# Sheet1.net
KiCad netlist of a schematic drawn in Altium Designer
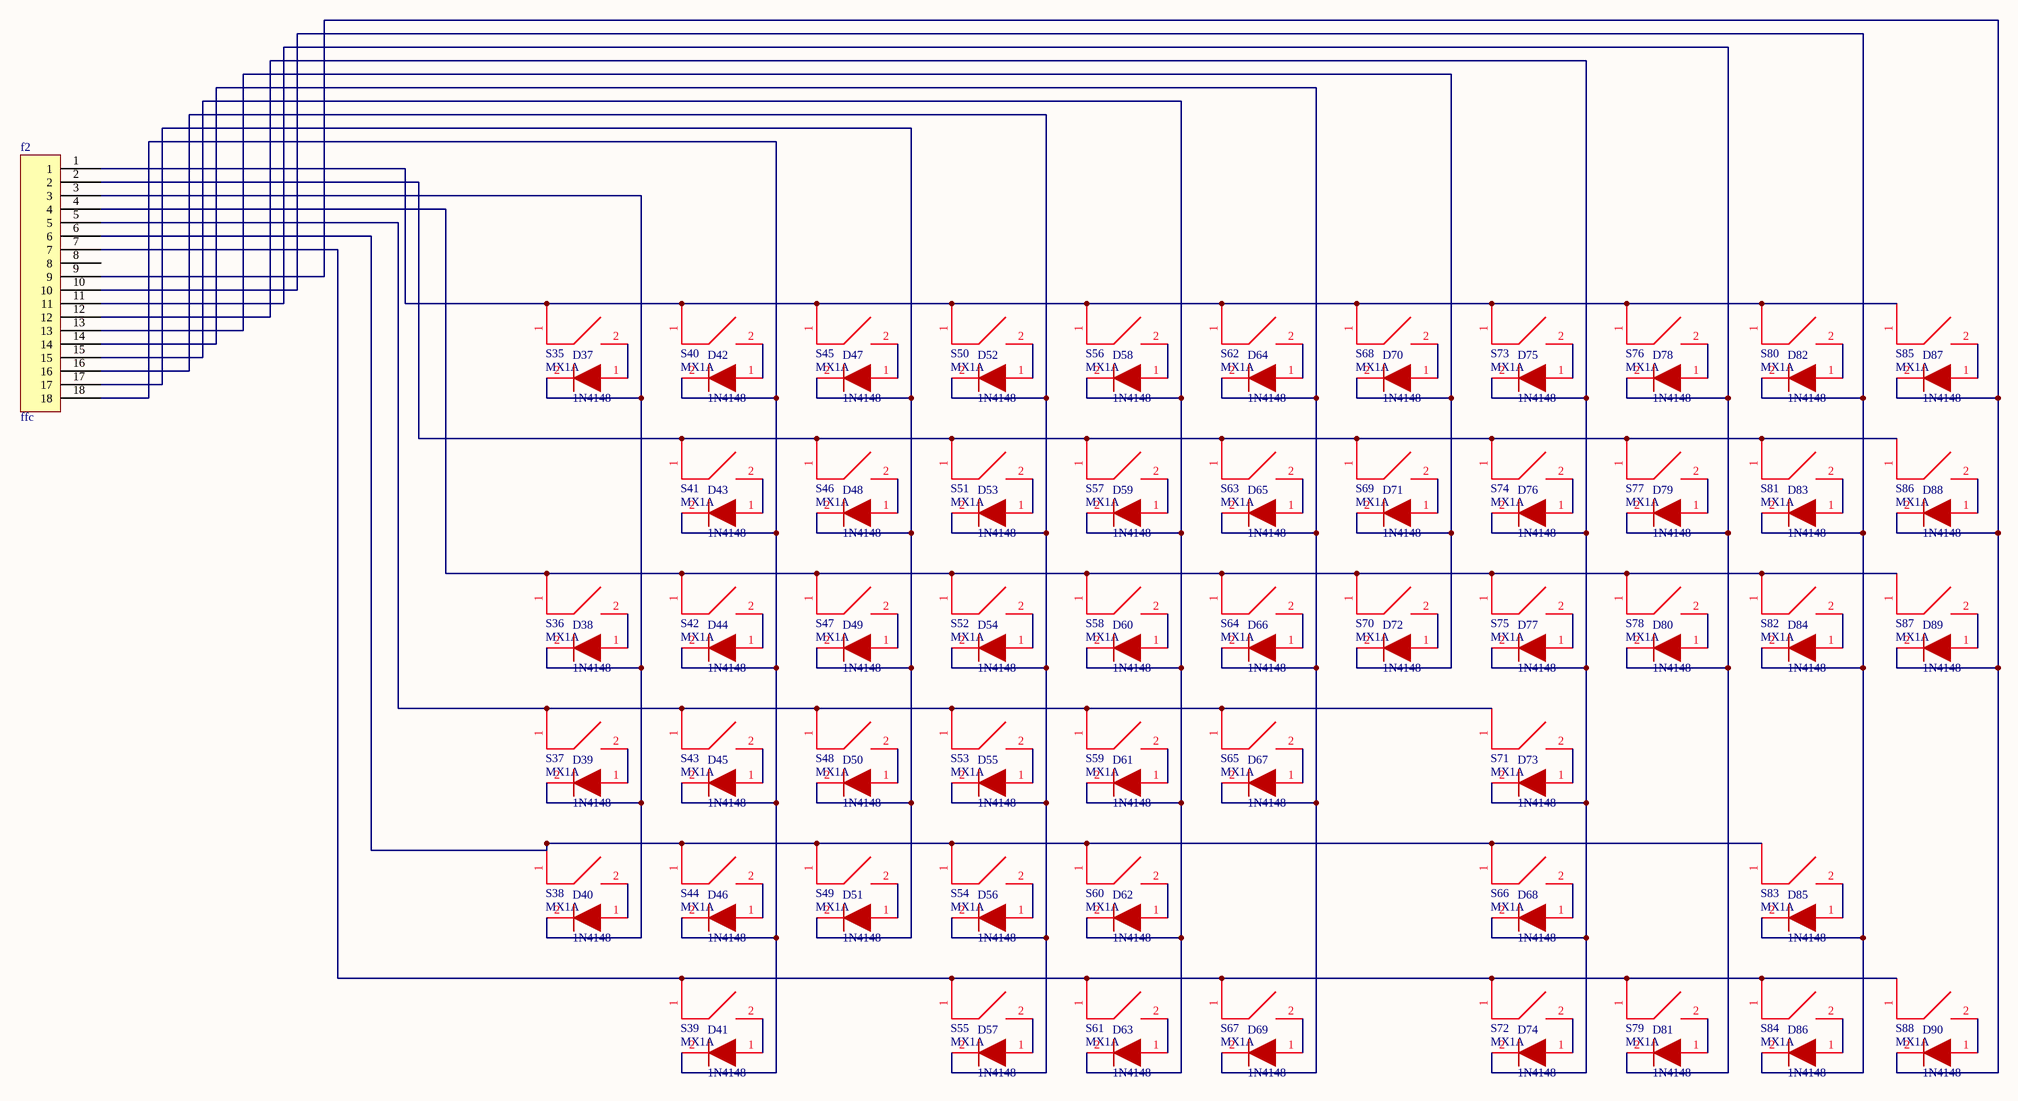
[diagram p0: Sheet1.SchDoc]

(export (version "E")
  (design (tool "Eeschema 10.0.6"))
  (components
    (comp (ref "D37")
      (value "1N4148")
      (footprint "SOD323")
      (description "二极管")
      (libsource (lib "keyboard") (part "1N4148"))
    )
    (comp (ref "D38")
      (value "1N4148")
      (footprint "SOD323")
      (description "二极管")
      (libsource (lib "keyboard") (part "1N4148"))
    )
    (comp (ref "D39")
      (value "1N4148")
      (footprint "SOD323")
      (description "二极管")
      (libsource (lib "keyboard") (part "1N4148"))
    )
    (comp (ref "D40")
      (value "1N4148")
      (footprint "SOD323")
      (description "二极管")
      (libsource (lib "keyboard") (part "1N4148"))
    )
    (comp (ref "D41")
      (value "1N4148")
      (footprint "SOD323")
      (description "二极管")
      (libsource (lib "keyboard") (part "1N4148"))
    )
    (comp (ref "D42")
      (value "1N4148")
      (footprint "SOD323")
      (description "二极管")
      (libsource (lib "keyboard") (part "1N4148"))
    )
    (comp (ref "D43")
      (value "1N4148")
      (footprint "SOD323")
      (description "二极管")
      (libsource (lib "keyboard") (part "1N4148"))
    )
    (comp (ref "D44")
      (value "1N4148")
      (footprint "SOD323")
      (description "二极管")
      (libsource (lib "keyboard") (part "1N4148"))
    )
    (comp (ref "D45")
      (value "1N4148")
      (footprint "SOD323")
      (description "二极管")
      (libsource (lib "keyboard") (part "1N4148"))
    )
    (comp (ref "D46")
      (value "1N4148")
      (footprint "SOD323")
      (description "二极管")
      (libsource (lib "keyboard") (part "1N4148"))
    )
    (comp (ref "D47")
      (value "1N4148")
      (footprint "SOD323")
      (description "二极管")
      (libsource (lib "keyboard") (part "1N4148"))
    )
    (comp (ref "D48")
      (value "1N4148")
      (footprint "SOD323")
      (description "二极管")
      (libsource (lib "keyboard") (part "1N4148"))
    )
    (comp (ref "D49")
      (value "1N4148")
      (footprint "SOD323")
      (description "二极管")
      (libsource (lib "keyboard") (part "1N4148"))
    )
    (comp (ref "D50")
      (value "1N4148")
      (footprint "SOD323")
      (description "二极管")
      (libsource (lib "keyboard") (part "1N4148"))
    )
    (comp (ref "D51")
      (value "1N4148")
      (footprint "SOD323")
      (description "二极管")
      (libsource (lib "keyboard") (part "1N4148"))
    )
    (comp (ref "D52")
      (value "1N4148")
      (footprint "SOD323")
      (description "二极管")
      (libsource (lib "keyboard") (part "1N4148"))
    )
    (comp (ref "D53")
      (value "1N4148")
      (footprint "SOD323")
      (description "二极管")
      (libsource (lib "keyboard") (part "1N4148"))
    )
    (comp (ref "D54")
      (value "1N4148")
      (footprint "SOD323")
      (description "二极管")
      (libsource (lib "keyboard") (part "1N4148"))
    )
    (comp (ref "D55")
      (value "1N4148")
      (footprint "SOD323")
      (description "二极管")
      (libsource (lib "keyboard") (part "1N4148"))
    )
    (comp (ref "D56")
      (value "1N4148")
      (footprint "SOD323")
      (description "二极管")
      (libsource (lib "keyboard") (part "1N4148"))
    )
    (comp (ref "D57")
      (value "1N4148")
      (footprint "SOD323")
      (description "二极管")
      (libsource (lib "keyboard") (part "1N4148"))
    )
    (comp (ref "D58")
      (value "1N4148")
      (footprint "SOD323")
      (description "二极管")
      (libsource (lib "keyboard") (part "1N4148"))
    )
    (comp (ref "D59")
      (value "1N4148")
      (footprint "SOD323")
      (description "二极管")
      (libsource (lib "keyboard") (part "1N4148"))
    )
    (comp (ref "D60")
      (value "1N4148")
      (footprint "SOD323")
      (description "二极管")
      (libsource (lib "keyboard") (part "1N4148"))
    )
    (comp (ref "D61")
      (value "1N4148")
      (footprint "SOD323")
      (description "二极管")
      (libsource (lib "keyboard") (part "1N4148"))
    )
    (comp (ref "D62")
      (value "1N4148")
      (footprint "SOD323")
      (description "二极管")
      (libsource (lib "keyboard") (part "1N4148"))
    )
    (comp (ref "D63")
      (value "1N4148")
      (footprint "SOD323")
      (description "二极管")
      (libsource (lib "keyboard") (part "1N4148"))
    )
    (comp (ref "D64")
      (value "1N4148")
      (footprint "SOD323")
      (description "二极管")
      (libsource (lib "keyboard") (part "1N4148"))
    )
    (comp (ref "D65")
      (value "1N4148")
      (footprint "SOD323")
      (description "二极管")
      (libsource (lib "keyboard") (part "1N4148"))
    )
    (comp (ref "D66")
      (value "1N4148")
      (footprint "SOD323")
      (description "二极管")
      (libsource (lib "keyboard") (part "1N4148"))
    )
    (comp (ref "D67")
      (value "1N4148")
      (footprint "SOD323")
      (description "二极管")
      (libsource (lib "keyboard") (part "1N4148"))
    )
    (comp (ref "D68")
      (value "1N4148")
      (footprint "SOD323")
      (description "二极管")
      (libsource (lib "keyboard") (part "1N4148"))
    )
    (comp (ref "D69")
      (value "1N4148")
      (footprint "SOD323")
      (description "二极管")
      (libsource (lib "keyboard") (part "1N4148"))
    )
    (comp (ref "D70")
      (value "1N4148")
      (footprint "SOD323")
      (description "二极管")
      (libsource (lib "keyboard") (part "1N4148"))
    )
    (comp (ref "D71")
      (value "1N4148")
      (footprint "SOD323")
      (description "二极管")
      (libsource (lib "keyboard") (part "1N4148"))
    )
    (comp (ref "D72")
      (value "1N4148")
      (footprint "SOD323")
      (description "二极管")
      (libsource (lib "keyboard") (part "1N4148"))
    )
    (comp (ref "D73")
      (value "1N4148")
      (footprint "SOD323")
      (description "二极管")
      (libsource (lib "keyboard") (part "1N4148"))
    )
    (comp (ref "D74")
      (value "1N4148")
      (footprint "SOD323")
      (description "二极管")
      (libsource (lib "keyboard") (part "1N4148"))
    )
    (comp (ref "D75")
      (value "1N4148")
      (footprint "SOD323")
      (description "二极管")
      (libsource (lib "keyboard") (part "1N4148"))
    )
    (comp (ref "D76")
      (value "1N4148")
      (footprint "SOD323")
      (description "二极管")
      (libsource (lib "keyboard") (part "1N4148"))
    )
    (comp (ref "D77")
      (value "1N4148")
      (footprint "SOD323")
      (description "二极管")
      (libsource (lib "keyboard") (part "1N4148"))
    )
    (comp (ref "D78")
      (value "1N4148")
      (footprint "SOD323")
      (description "二极管")
      (libsource (lib "keyboard") (part "1N4148"))
    )
    (comp (ref "D79")
      (value "1N4148")
      (footprint "SOD323")
      (description "二极管")
      (libsource (lib "keyboard") (part "1N4148"))
    )
    (comp (ref "D80")
      (value "1N4148")
      (footprint "SOD323")
      (description "二极管")
      (libsource (lib "keyboard") (part "1N4148"))
    )
    (comp (ref "D81")
      (value "1N4148")
      (footprint "SOD323")
      (description "二极管")
      (libsource (lib "keyboard") (part "1N4148"))
    )
    (comp (ref "D82")
      (value "1N4148")
      (footprint "SOD323")
      (description "二极管")
      (libsource (lib "keyboard") (part "1N4148"))
    )
    (comp (ref "D83")
      (value "1N4148")
      (footprint "SOD323")
      (description "二极管")
      (libsource (lib "keyboard") (part "1N4148"))
    )
    (comp (ref "D84")
      (value "1N4148")
      (footprint "SOD323")
      (description "二极管")
      (libsource (lib "keyboard") (part "1N4148"))
    )
    (comp (ref "D85")
      (value "1N4148")
      (footprint "SOD323")
      (description "二极管")
      (libsource (lib "keyboard") (part "1N4148"))
    )
    (comp (ref "D86")
      (value "1N4148")
      (footprint "SOD323")
      (description "二极管")
      (libsource (lib "keyboard") (part "1N4148"))
    )
    (comp (ref "D87")
      (value "1N4148")
      (footprint "SOD323")
      (description "二极管")
      (libsource (lib "keyboard") (part "1N4148"))
    )
    (comp (ref "D88")
      (value "1N4148")
      (footprint "SOD323")
      (description "二极管")
      (libsource (lib "keyboard") (part "1N4148"))
    )
    (comp (ref "D89")
      (value "1N4148")
      (footprint "SOD323")
      (description "二极管")
      (libsource (lib "keyboard") (part "1N4148"))
    )
    (comp (ref "D90")
      (value "1N4148")
      (footprint "SOD323")
      (description "二极管")
      (libsource (lib "keyboard") (part "1N4148"))
    )
    (comp (ref "f2") (value "ffc") (footprint "FFC") (libsource (lib "keyboard") (part "ffc")))
    (comp (ref "S35")
      (value "MX1A")
      (footprint "KEY")
      (description "按键")
      (libsource (lib "keyboard") (part "MX1A"))
    )
    (comp (ref "S36")
      (value "MX1A")
      (footprint "KEY")
      (description "按键")
      (libsource (lib "keyboard") (part "MX1A"))
    )
    (comp (ref "S37")
      (value "MX1A")
      (footprint "KEY")
      (description "按键")
      (libsource (lib "keyboard") (part "MX1A"))
    )
    (comp (ref "S38")
      (value "MX1A")
      (footprint "KEY")
      (description "按键")
      (libsource (lib "keyboard") (part "MX1A"))
    )
    (comp (ref "S39")
      (value "MX1A")
      (footprint "KEY")
      (description "按键")
      (libsource (lib "keyboard") (part "MX1A"))
    )
    (comp (ref "S40")
      (value "MX1A")
      (footprint "KEY")
      (description "按键")
      (libsource (lib "keyboard") (part "MX1A"))
    )
    (comp (ref "S41")
      (value "MX1A")
      (footprint "KEY")
      (description "按键")
      (libsource (lib "keyboard") (part "MX1A"))
    )
    (comp (ref "S42")
      (value "MX1A")
      (footprint "KEY")
      (description "按键")
      (libsource (lib "keyboard") (part "MX1A"))
    )
    (comp (ref "S43")
      (value "MX1A")
      (footprint "KEY")
      (description "按键")
      (libsource (lib "keyboard") (part "MX1A"))
    )
    (comp (ref "S44")
      (value "MX1A")
      (footprint "KEY")
      (description "按键")
      (libsource (lib "keyboard") (part "MX1A"))
    )
    (comp (ref "S45")
      (value "MX1A")
      (footprint "KEY")
      (description "按键")
      (libsource (lib "keyboard") (part "MX1A"))
    )
    (comp (ref "S46")
      (value "MX1A")
      (footprint "KEY")
      (description "按键")
      (libsource (lib "keyboard") (part "MX1A"))
    )
    (comp (ref "S47")
      (value "MX1A")
      (footprint "KEY")
      (description "按键")
      (libsource (lib "keyboard") (part "MX1A"))
    )
    (comp (ref "S48")
      (value "MX1A")
      (footprint "KEY")
      (description "按键")
      (libsource (lib "keyboard") (part "MX1A"))
    )
    (comp (ref "S49")
      (value "MX1A")
      (footprint "KEY")
      (description "按键")
      (libsource (lib "keyboard") (part "MX1A"))
    )
    (comp (ref "S50")
      (value "MX1A")
      (footprint "KEY")
      (description "按键")
      (libsource (lib "keyboard") (part "MX1A"))
    )
    (comp (ref "S51")
      (value "MX1A")
      (footprint "KEY")
      (description "按键")
      (libsource (lib "keyboard") (part "MX1A"))
    )
    (comp (ref "S52")
      (value "MX1A")
      (footprint "KEY")
      (description "按键")
      (libsource (lib "keyboard") (part "MX1A"))
    )
    (comp (ref "S53")
      (value "MX1A")
      (footprint "KEY")
      (description "按键")
      (libsource (lib "keyboard") (part "MX1A"))
    )
    (comp (ref "S54")
      (value "MX1A")
      (footprint "KEY")
      (description "按键")
      (libsource (lib "keyboard") (part "MX1A"))
    )
    (comp (ref "S55")
      (value "MX1A")
      (footprint "KEY")
      (description "按键")
      (libsource (lib "keyboard") (part "MX1A"))
    )
    (comp (ref "S56")
      (value "MX1A")
      (footprint "KEY")
      (description "按键")
      (libsource (lib "keyboard") (part "MX1A"))
    )
    (comp (ref "S57")
      (value "MX1A")
      (footprint "KEY")
      (description "按键")
      (libsource (lib "keyboard") (part "MX1A"))
    )
    (comp (ref "S58")
      (value "MX1A")
      (footprint "KEY")
      (description "按键")
      (libsource (lib "keyboard") (part "MX1A"))
    )
    (comp (ref "S59")
      (value "MX1A")
      (footprint "KEY")
      (description "按键")
      (libsource (lib "keyboard") (part "MX1A"))
    )
    (comp (ref "S60")
      (value "MX1A")
      (footprint "KEY")
      (description "按键")
      (libsource (lib "keyboard") (part "MX1A"))
    )
    (comp (ref "S61")
      (value "MX1A")
      (footprint "KEY")
      (description "按键")
      (libsource (lib "keyboard") (part "MX1A"))
    )
    (comp (ref "S62")
      (value "MX1A")
      (footprint "KEY")
      (description "按键")
      (libsource (lib "keyboard") (part "MX1A"))
    )
    (comp (ref "S63")
      (value "MX1A")
      (footprint "KEY")
      (description "按键")
      (libsource (lib "keyboard") (part "MX1A"))
    )
    (comp (ref "S64")
      (value "MX1A")
      (footprint "KEY")
      (description "按键")
      (libsource (lib "keyboard") (part "MX1A"))
    )
    (comp (ref "S65")
      (value "MX1A")
      (footprint "KEY")
      (description "按键")
      (libsource (lib "keyboard") (part "MX1A"))
    )
    (comp (ref "S66")
      (value "MX1A")
      (footprint "KEY")
      (description "按键")
      (libsource (lib "keyboard") (part "MX1A"))
    )
    (comp (ref "S67")
      (value "MX1A")
      (footprint "KEY")
      (description "按键")
      (libsource (lib "keyboard") (part "MX1A"))
    )
    (comp (ref "S68")
      (value "MX1A")
      (footprint "KEY")
      (description "按键")
      (libsource (lib "keyboard") (part "MX1A"))
    )
    (comp (ref "S69")
      (value "MX1A")
      (footprint "KEY")
      (description "按键")
      (libsource (lib "keyboard") (part "MX1A"))
    )
    (comp (ref "S70")
      (value "MX1A")
      (footprint "KEY")
      (description "按键")
      (libsource (lib "keyboard") (part "MX1A"))
    )
    (comp (ref "S71")
      (value "MX1A")
      (footprint "KEY")
      (description "按键")
      (libsource (lib "keyboard") (part "MX1A"))
    )
    (comp (ref "S72")
      (value "MX1A")
      (footprint "KEY")
      (description "按键")
      (libsource (lib "keyboard") (part "MX1A"))
    )
    (comp (ref "S73")
      (value "MX1A")
      (footprint "KEY")
      (description "按键")
      (libsource (lib "keyboard") (part "MX1A"))
    )
    (comp (ref "S74")
      (value "MX1A")
      (footprint "KEY")
      (description "按键")
      (libsource (lib "keyboard") (part "MX1A"))
    )
    (comp (ref "S75")
      (value "MX1A")
      (footprint "KEY")
      (description "按键")
      (libsource (lib "keyboard") (part "MX1A"))
    )
    (comp (ref "S76")
      (value "MX1A")
      (footprint "KEY")
      (description "按键")
      (libsource (lib "keyboard") (part "MX1A"))
    )
    (comp (ref "S77")
      (value "MX1A")
      (footprint "KEY")
      (description "按键")
      (libsource (lib "keyboard") (part "MX1A"))
    )
    (comp (ref "S78")
      (value "MX1A")
      (footprint "KEY")
      (description "按键")
      (libsource (lib "keyboard") (part "MX1A"))
    )
    (comp (ref "S79")
      (value "MX1A")
      (footprint "KEY")
      (description "按键")
      (libsource (lib "keyboard") (part "MX1A"))
    )
    (comp (ref "S80")
      (value "MX1A")
      (footprint "KEY")
      (description "按键")
      (libsource (lib "keyboard") (part "MX1A"))
    )
    (comp (ref "S81")
      (value "MX1A")
      (footprint "KEY")
      (description "按键")
      (libsource (lib "keyboard") (part "MX1A"))
    )
    (comp (ref "S82")
      (value "MX1A")
      (footprint "KEY")
      (description "按键")
      (libsource (lib "keyboard") (part "MX1A"))
    )
    (comp (ref "S83")
      (value "MX1A")
      (footprint "KEY")
      (description "按键")
      (libsource (lib "keyboard") (part "MX1A"))
    )
    (comp (ref "S84")
      (value "MX1A")
      (footprint "KEY")
      (description "按键")
      (libsource (lib "keyboard") (part "MX1A"))
    )
    (comp (ref "S85")
      (value "MX1A")
      (footprint "KEY")
      (description "按键")
      (libsource (lib "keyboard") (part "MX1A"))
    )
    (comp (ref "S86")
      (value "MX1A")
      (footprint "KEY")
      (description "按键")
      (libsource (lib "keyboard") (part "MX1A"))
    )
    (comp (ref "S87")
      (value "MX1A")
      (footprint "KEY")
      (description "按键")
      (libsource (lib "keyboard") (part "MX1A"))
    )
    (comp (ref "S88")
      (value "MX1A")
      (footprint "KEY")
      (description "按键")
      (libsource (lib "keyboard") (part "MX1A"))
    )
  )
  (nets
    (net (code "1") (name "Net-(D37-Pad1)") (class "Default")
      (node (ref "D37") (pin "1") (pinfunction "1_1") (pintype "passive"))
      (node (ref "S35") (pin "2") (pinfunction "2_2") (pintype "passive"))
    )
    (net (code "2") (name "Net-(D37-Pad2)") (class "Default")
      (node (ref "D37") (pin "2") (pinfunction "2_2") (pintype "passive"))
      (node (ref "D38") (pin "2") (pinfunction "2_2") (pintype "passive"))
      (node (ref "D39") (pin "2") (pinfunction "2_2") (pintype "passive"))
      (node (ref "D40") (pin "2") (pinfunction "2_2") (pintype "passive"))
      (node (ref "f2") (pin "3") (pinfunction "3_3") (pintype "passive"))
    )
    (net (code "3") (name "Net-(D38-Pad1)") (class "Default")
      (node (ref "D38") (pin "1") (pinfunction "1_1") (pintype "passive"))
      (node (ref "S36") (pin "2") (pinfunction "2_2") (pintype "passive"))
    )
    (net (code "4") (name "Net-(D39-Pad1)") (class "Default")
      (node (ref "D39") (pin "1") (pinfunction "1_1") (pintype "passive"))
      (node (ref "S37") (pin "2") (pinfunction "2_2") (pintype "passive"))
    )
    (net (code "5") (name "Net-(D40-Pad1)") (class "Default")
      (node (ref "D40") (pin "1") (pinfunction "1_1") (pintype "passive"))
      (node (ref "S38") (pin "2") (pinfunction "2_2") (pintype "passive"))
    )
    (net (code "6") (name "Net-(D41-Pad1)") (class "Default")
      (node (ref "D41") (pin "1") (pinfunction "1_1") (pintype "passive"))
      (node (ref "S39") (pin "2") (pinfunction "2_2") (pintype "passive"))
    )
    (net (code "7") (name "Net-(D41-Pad2)") (class "Default")
      (node (ref "D41") (pin "2") (pinfunction "2_2") (pintype "passive"))
      (node (ref "D42") (pin "2") (pinfunction "2_2") (pintype "passive"))
      (node (ref "D43") (pin "2") (pinfunction "2_2") (pintype "passive"))
      (node (ref "D44") (pin "2") (pinfunction "2_2") (pintype "passive"))
      (node (ref "D45") (pin "2") (pinfunction "2_2") (pintype "passive"))
      (node (ref "D46") (pin "2") (pinfunction "2_2") (pintype "passive"))
      (node (ref "f2") (pin "18") (pinfunction "18_18") (pintype "passive"))
    )
    (net (code "8") (name "Net-(D42-Pad1)") (class "Default")
      (node (ref "D42") (pin "1") (pinfunction "1_1") (pintype "passive"))
      (node (ref "S40") (pin "2") (pinfunction "2_2") (pintype "passive"))
    )
    (net (code "9") (name "Net-(D43-Pad1)") (class "Default")
      (node (ref "D43") (pin "1") (pinfunction "1_1") (pintype "passive"))
      (node (ref "S41") (pin "2") (pinfunction "2_2") (pintype "passive"))
    )
    (net (code "10") (name "Net-(D44-Pad1)") (class "Default")
      (node (ref "D44") (pin "1") (pinfunction "1_1") (pintype "passive"))
      (node (ref "S42") (pin "2") (pinfunction "2_2") (pintype "passive"))
    )
    (net (code "11") (name "Net-(D45-Pad1)") (class "Default")
      (node (ref "D45") (pin "1") (pinfunction "1_1") (pintype "passive"))
      (node (ref "S43") (pin "2") (pinfunction "2_2") (pintype "passive"))
    )
    (net (code "12") (name "Net-(D46-Pad1)") (class "Default")
      (node (ref "D46") (pin "1") (pinfunction "1_1") (pintype "passive"))
      (node (ref "S44") (pin "2") (pinfunction "2_2") (pintype "passive"))
    )
    (net (code "13") (name "Net-(D47-Pad1)") (class "Default")
      (node (ref "D47") (pin "1") (pinfunction "1_1") (pintype "passive"))
      (node (ref "S45") (pin "2") (pinfunction "2_2") (pintype "passive"))
    )
    (net (code "14") (name "Net-(D47-Pad2)") (class "Default")
      (node (ref "D47") (pin "2") (pinfunction "2_2") (pintype "passive"))
      (node (ref "D48") (pin "2") (pinfunction "2_2") (pintype "passive"))
      (node (ref "D49") (pin "2") (pinfunction "2_2") (pintype "passive"))
      (node (ref "D50") (pin "2") (pinfunction "2_2") (pintype "passive"))
      (node (ref "D51") (pin "2") (pinfunction "2_2") (pintype "passive"))
      (node (ref "f2") (pin "17") (pinfunction "17_17") (pintype "passive"))
    )
    (net (code "15") (name "Net-(D48-Pad1)") (class "Default")
      (node (ref "D48") (pin "1") (pinfunction "1_1") (pintype "passive"))
      (node (ref "S46") (pin "2") (pinfunction "2_2") (pintype "passive"))
    )
    (net (code "16") (name "Net-(D49-Pad1)") (class "Default")
      (node (ref "D49") (pin "1") (pinfunction "1_1") (pintype "passive"))
      (node (ref "S47") (pin "2") (pinfunction "2_2") (pintype "passive"))
    )
    (net (code "17") (name "Net-(D50-Pad1)") (class "Default")
      (node (ref "D50") (pin "1") (pinfunction "1_1") (pintype "passive"))
      (node (ref "S48") (pin "2") (pinfunction "2_2") (pintype "passive"))
    )
    (net (code "18") (name "Net-(D51-Pad1)") (class "Default")
      (node (ref "D51") (pin "1") (pinfunction "1_1") (pintype "passive"))
      (node (ref "S49") (pin "2") (pinfunction "2_2") (pintype "passive"))
    )
    (net (code "19") (name "Net-(D52-Pad1)") (class "Default")
      (node (ref "D52") (pin "1") (pinfunction "1_1") (pintype "passive"))
      (node (ref "S50") (pin "2") (pinfunction "2_2") (pintype "passive"))
    )
    (net (code "20") (name "Net-(D52-Pad2)") (class "Default")
      (node (ref "D52") (pin "2") (pinfunction "2_2") (pintype "passive"))
      (node (ref "D53") (pin "2") (pinfunction "2_2") (pintype "passive"))
      (node (ref "D54") (pin "2") (pinfunction "2_2") (pintype "passive"))
      (node (ref "D55") (pin "2") (pinfunction "2_2") (pintype "passive"))
      (node (ref "D56") (pin "2") (pinfunction "2_2") (pintype "passive"))
      (node (ref "D57") (pin "2") (pinfunction "2_2") (pintype "passive"))
      (node (ref "f2") (pin "16") (pinfunction "16_16") (pintype "passive"))
    )
    (net (code "21") (name "Net-(D53-Pad1)") (class "Default")
      (node (ref "D53") (pin "1") (pinfunction "1_1") (pintype "passive"))
      (node (ref "S51") (pin "2") (pinfunction "2_2") (pintype "passive"))
    )
    (net (code "22") (name "Net-(D54-Pad1)") (class "Default")
      (node (ref "D54") (pin "1") (pinfunction "1_1") (pintype "passive"))
      (node (ref "S52") (pin "2") (pinfunction "2_2") (pintype "passive"))
    )
    (net (code "23") (name "Net-(D55-Pad1)") (class "Default")
      (node (ref "D55") (pin "1") (pinfunction "1_1") (pintype "passive"))
      (node (ref "S53") (pin "2") (pinfunction "2_2") (pintype "passive"))
    )
    (net (code "24") (name "Net-(D56-Pad1)") (class "Default")
      (node (ref "D56") (pin "1") (pinfunction "1_1") (pintype "passive"))
      (node (ref "S54") (pin "2") (pinfunction "2_2") (pintype "passive"))
    )
    (net (code "25") (name "Net-(D57-Pad1)") (class "Default")
      (node (ref "D57") (pin "1") (pinfunction "1_1") (pintype "passive"))
      (node (ref "S55") (pin "2") (pinfunction "2_2") (pintype "passive"))
    )
    (net (code "26") (name "Net-(D58-Pad1)") (class "Default")
      (node (ref "D58") (pin "1") (pinfunction "1_1") (pintype "passive"))
      (node (ref "S56") (pin "2") (pinfunction "2_2") (pintype "passive"))
    )
    (net (code "27") (name "Net-(D58-Pad2)") (class "Default")
      (node (ref "D58") (pin "2") (pinfunction "2_2") (pintype "passive"))
      (node (ref "D59") (pin "2") (pinfunction "2_2") (pintype "passive"))
      (node (ref "D60") (pin "2") (pinfunction "2_2") (pintype "passive"))
      (node (ref "D61") (pin "2") (pinfunction "2_2") (pintype "passive"))
      (node (ref "D62") (pin "2") (pinfunction "2_2") (pintype "passive"))
      (node (ref "D63") (pin "2") (pinfunction "2_2") (pintype "passive"))
      (node (ref "f2") (pin "15") (pinfunction "15_15") (pintype "passive"))
    )
    (net (code "28") (name "Net-(D59-Pad1)") (class "Default")
      (node (ref "D59") (pin "1") (pinfunction "1_1") (pintype "passive"))
      (node (ref "S57") (pin "2") (pinfunction "2_2") (pintype "passive"))
    )
    (net (code "29") (name "Net-(D60-Pad1)") (class "Default")
      (node (ref "D60") (pin "1") (pinfunction "1_1") (pintype "passive"))
      (node (ref "S58") (pin "2") (pinfunction "2_2") (pintype "passive"))
    )
    (net (code "30") (name "Net-(D61-Pad1)") (class "Default")
      (node (ref "D61") (pin "1") (pinfunction "1_1") (pintype "passive"))
      (node (ref "S59") (pin "2") (pinfunction "2_2") (pintype "passive"))
    )
    (net (code "31") (name "Net-(D62-Pad1)") (class "Default")
      (node (ref "D62") (pin "1") (pinfunction "1_1") (pintype "passive"))
      (node (ref "S60") (pin "2") (pinfunction "2_2") (pintype "passive"))
    )
    (net (code "32") (name "Net-(D63-Pad1)") (class "Default")
      (node (ref "D63") (pin "1") (pinfunction "1_1") (pintype "passive"))
      (node (ref "S61") (pin "2") (pinfunction "2_2") (pintype "passive"))
    )
    (net (code "33") (name "Net-(D64-Pad1)") (class "Default")
      (node (ref "D64") (pin "1") (pinfunction "1_1") (pintype "passive"))
      (node (ref "S62") (pin "2") (pinfunction "2_2") (pintype "passive"))
    )
    (net (code "34") (name "Net-(D64-Pad2)") (class "Default")
      (node (ref "D64") (pin "2") (pinfunction "2_2") (pintype "passive"))
      (node (ref "D65") (pin "2") (pinfunction "2_2") (pintype "passive"))
      (node (ref "D66") (pin "2") (pinfunction "2_2") (pintype "passive"))
      (node (ref "D67") (pin "2") (pinfunction "2_2") (pintype "passive"))
      (node (ref "D69") (pin "2") (pinfunction "2_2") (pintype "passive"))
      (node (ref "f2") (pin "14") (pinfunction "14_14") (pintype "passive"))
    )
    (net (code "35") (name "Net-(D65-Pad1)") (class "Default")
      (node (ref "D65") (pin "1") (pinfunction "1_1") (pintype "passive"))
      (node (ref "S63") (pin "2") (pinfunction "2_2") (pintype "passive"))
    )
    (net (code "36") (name "Net-(D66-Pad1)") (class "Default")
      (node (ref "D66") (pin "1") (pinfunction "1_1") (pintype "passive"))
      (node (ref "S64") (pin "2") (pinfunction "2_2") (pintype "passive"))
    )
    (net (code "37") (name "Net-(D67-Pad1)") (class "Default")
      (node (ref "D67") (pin "1") (pinfunction "1_1") (pintype "passive"))
      (node (ref "S65") (pin "2") (pinfunction "2_2") (pintype "passive"))
    )
    (net (code "38") (name "Net-(D68-Pad1)") (class "Default")
      (node (ref "D68") (pin "1") (pinfunction "1_1") (pintype "passive"))
      (node (ref "S66") (pin "2") (pinfunction "2_2") (pintype "passive"))
    )
    (net (code "39") (name "Net-(D68-Pad2)") (class "Default")
      (node (ref "D68") (pin "2") (pinfunction "2_2") (pintype "passive"))
      (node (ref "D73") (pin "2") (pinfunction "2_2") (pintype "passive"))
      (node (ref "D74") (pin "2") (pinfunction "2_2") (pintype "passive"))
      (node (ref "D75") (pin "2") (pinfunction "2_2") (pintype "passive"))
      (node (ref "D76") (pin "2") (pinfunction "2_2") (pintype "passive"))
      (node (ref "D77") (pin "2") (pinfunction "2_2") (pintype "passive"))
      (node (ref "f2") (pin "12") (pinfunction "12_12") (pintype "passive"))
    )
    (net (code "40") (name "Net-(D69-Pad1)") (class "Default")
      (node (ref "D69") (pin "1") (pinfunction "1_1") (pintype "passive"))
      (node (ref "S67") (pin "2") (pinfunction "2_2") (pintype "passive"))
    )
    (net (code "41") (name "Net-(D70-Pad1)") (class "Default")
      (node (ref "D70") (pin "1") (pinfunction "1_1") (pintype "passive"))
      (node (ref "S68") (pin "2") (pinfunction "2_2") (pintype "passive"))
    )
    (net (code "42") (name "Net-(D70-Pad2)") (class "Default")
      (node (ref "D70") (pin "2") (pinfunction "2_2") (pintype "passive"))
      (node (ref "D71") (pin "2") (pinfunction "2_2") (pintype "passive"))
      (node (ref "D72") (pin "2") (pinfunction "2_2") (pintype "passive"))
      (node (ref "f2") (pin "13") (pinfunction "13_13") (pintype "passive"))
    )
    (net (code "43") (name "Net-(D71-Pad1)") (class "Default")
      (node (ref "D71") (pin "1") (pinfunction "1_1") (pintype "passive"))
      (node (ref "S69") (pin "2") (pinfunction "2_2") (pintype "passive"))
    )
    (net (code "44") (name "Net-(D72-Pad1)") (class "Default")
      (node (ref "D72") (pin "1") (pinfunction "1_1") (pintype "passive"))
      (node (ref "S70") (pin "2") (pinfunction "2_2") (pintype "passive"))
    )
    (net (code "45") (name "Net-(D73-Pad1)") (class "Default")
      (node (ref "D73") (pin "1") (pinfunction "1_1") (pintype "passive"))
      (node (ref "S71") (pin "2") (pinfunction "2_2") (pintype "passive"))
    )
    (net (code "46") (name "Net-(D74-Pad1)") (class "Default")
      (node (ref "D74") (pin "1") (pinfunction "1_1") (pintype "passive"))
      (node (ref "S72") (pin "2") (pinfunction "2_2") (pintype "passive"))
    )
    (net (code "47") (name "Net-(D75-Pad1)") (class "Default")
      (node (ref "D75") (pin "1") (pinfunction "1_1") (pintype "passive"))
      (node (ref "S73") (pin "2") (pinfunction "2_2") (pintype "passive"))
    )
    (net (code "48") (name "Net-(D76-Pad1)") (class "Default")
      (node (ref "D76") (pin "1") (pinfunction "1_1") (pintype "passive"))
      (node (ref "S74") (pin "2") (pinfunction "2_2") (pintype "passive"))
    )
    (net (code "49") (name "Net-(D77-Pad1)") (class "Default")
      (node (ref "D77") (pin "1") (pinfunction "1_1") (pintype "passive"))
      (node (ref "S75") (pin "2") (pinfunction "2_2") (pintype "passive"))
    )
    (net (code "50") (name "Net-(D78-Pad1)") (class "Default")
      (node (ref "D78") (pin "1") (pinfunction "1_1") (pintype "passive"))
      (node (ref "S76") (pin "2") (pinfunction "2_2") (pintype "passive"))
    )
    (net (code "51") (name "Net-(D78-Pad2)") (class "Default")
      (node (ref "D78") (pin "2") (pinfunction "2_2") (pintype "passive"))
      (node (ref "D79") (pin "2") (pinfunction "2_2") (pintype "passive"))
      (node (ref "D80") (pin "2") (pinfunction "2_2") (pintype "passive"))
      (node (ref "D81") (pin "2") (pinfunction "2_2") (pintype "passive"))
      (node (ref "f2") (pin "11") (pinfunction "11_11") (pintype "passive"))
    )
    (net (code "52") (name "Net-(D79-Pad1)") (class "Default")
      (node (ref "D79") (pin "1") (pinfunction "1_1") (pintype "passive"))
      (node (ref "S77") (pin "2") (pinfunction "2_2") (pintype "passive"))
    )
    (net (code "53") (name "Net-(D80-Pad1)") (class "Default")
      (node (ref "D80") (pin "1") (pinfunction "1_1") (pintype "passive"))
      (node (ref "S78") (pin "2") (pinfunction "2_2") (pintype "passive"))
    )
    (net (code "54") (name "Net-(D81-Pad1)") (class "Default")
      (node (ref "D81") (pin "1") (pinfunction "1_1") (pintype "passive"))
      (node (ref "S79") (pin "2") (pinfunction "2_2") (pintype "passive"))
    )
    (net (code "55") (name "Net-(D82-Pad1)") (class "Default")
      (node (ref "D82") (pin "1") (pinfunction "1_1") (pintype "passive"))
      (node (ref "S80") (pin "2") (pinfunction "2_2") (pintype "passive"))
    )
    (net (code "56") (name "Net-(D82-Pad2)") (class "Default")
      (node (ref "D82") (pin "2") (pinfunction "2_2") (pintype "passive"))
      (node (ref "D83") (pin "2") (pinfunction "2_2") (pintype "passive"))
      (node (ref "D84") (pin "2") (pinfunction "2_2") (pintype "passive"))
      (node (ref "D85") (pin "2") (pinfunction "2_2") (pintype "passive"))
      (node (ref "D86") (pin "2") (pinfunction "2_2") (pintype "passive"))
      (node (ref "f2") (pin "10") (pinfunction "10_10") (pintype "passive"))
    )
    (net (code "57") (name "Net-(D83-Pad1)") (class "Default")
      (node (ref "D83") (pin "1") (pinfunction "1_1") (pintype "passive"))
      (node (ref "S81") (pin "2") (pinfunction "2_2") (pintype "passive"))
    )
    (net (code "58") (name "Net-(D84-Pad1)") (class "Default")
      (node (ref "D84") (pin "1") (pinfunction "1_1") (pintype "passive"))
      (node (ref "S82") (pin "2") (pinfunction "2_2") (pintype "passive"))
    )
    (net (code "59") (name "Net-(D85-Pad1)") (class "Default")
      (node (ref "D85") (pin "1") (pinfunction "1_1") (pintype "passive"))
      (node (ref "S83") (pin "2") (pinfunction "2_2") (pintype "passive"))
    )
    (net (code "60") (name "Net-(D86-Pad1)") (class "Default")
      (node (ref "D86") (pin "1") (pinfunction "1_1") (pintype "passive"))
      (node (ref "S84") (pin "2") (pinfunction "2_2") (pintype "passive"))
    )
    (net (code "61") (name "Net-(D87-Pad1)") (class "Default")
      (node (ref "D87") (pin "1") (pinfunction "1_1") (pintype "passive"))
      (node (ref "S85") (pin "2") (pinfunction "2_2") (pintype "passive"))
    )
    (net (code "62") (name "Net-(D87-Pad2)") (class "Default")
      (node (ref "D87") (pin "2") (pinfunction "2_2") (pintype "passive"))
      (node (ref "D88") (pin "2") (pinfunction "2_2") (pintype "passive"))
      (node (ref "D89") (pin "2") (pinfunction "2_2") (pintype "passive"))
      (node (ref "D90") (pin "2") (pinfunction "2_2") (pintype "passive"))
      (node (ref "f2") (pin "9") (pinfunction "9_9") (pintype "passive"))
    )
    (net (code "63") (name "Net-(D88-Pad1)") (class "Default")
      (node (ref "D88") (pin "1") (pinfunction "1_1") (pintype "passive"))
      (node (ref "S86") (pin "2") (pinfunction "2_2") (pintype "passive"))
    )
    (net (code "64") (name "Net-(D89-Pad1)") (class "Default")
      (node (ref "D89") (pin "1") (pinfunction "1_1") (pintype "passive"))
      (node (ref "S87") (pin "2") (pinfunction "2_2") (pintype "passive"))
    )
    (net (code "65") (name "Net-(D90-Pad1)") (class "Default")
      (node (ref "D90") (pin "1") (pinfunction "1_1") (pintype "passive"))
      (node (ref "S88") (pin "2") (pinfunction "2_2") (pintype "passive"))
    )
    (net (code "66") (name "Net-(S35-Pad1)") (class "Default")
      (node (ref "S35") (pin "1") (pinfunction "1_1") (pintype "passive"))
      (node (ref "S40") (pin "1") (pinfunction "1_1") (pintype "passive"))
      (node (ref "S45") (pin "1") (pinfunction "1_1") (pintype "passive"))
      (node (ref "S50") (pin "1") (pinfunction "1_1") (pintype "passive"))
      (node (ref "S56") (pin "1") (pinfunction "1_1") (pintype "passive"))
      (node (ref "S62") (pin "1") (pinfunction "1_1") (pintype "passive"))
      (node (ref "S68") (pin "1") (pinfunction "1_1") (pintype "passive"))
      (node (ref "S73") (pin "1") (pinfunction "1_1") (pintype "passive"))
      (node (ref "S76") (pin "1") (pinfunction "1_1") (pintype "passive"))
      (node (ref "S80") (pin "1") (pinfunction "1_1") (pintype "passive"))
      (node (ref "S85") (pin "1") (pinfunction "1_1") (pintype "passive"))
      (node (ref "f2") (pin "1") (pinfunction "1_1") (pintype "passive"))
    )
    (net (code "67") (name "Net-(S36-Pad1)") (class "Default")
      (node (ref "S36") (pin "1") (pinfunction "1_1") (pintype "passive"))
      (node (ref "S42") (pin "1") (pinfunction "1_1") (pintype "passive"))
      (node (ref "S47") (pin "1") (pinfunction "1_1") (pintype "passive"))
      (node (ref "S52") (pin "1") (pinfunction "1_1") (pintype "passive"))
      (node (ref "S58") (pin "1") (pinfunction "1_1") (pintype "passive"))
      (node (ref "S64") (pin "1") (pinfunction "1_1") (pintype "passive"))
      (node (ref "S70") (pin "1") (pinfunction "1_1") (pintype "passive"))
      (node (ref "S75") (pin "1") (pinfunction "1_1") (pintype "passive"))
      (node (ref "S78") (pin "1") (pinfunction "1_1") (pintype "passive"))
      (node (ref "S82") (pin "1") (pinfunction "1_1") (pintype "passive"))
      (node (ref "S87") (pin "1") (pinfunction "1_1") (pintype "passive"))
      (node (ref "f2") (pin "4") (pinfunction "4_4") (pintype "passive"))
    )
    (net (code "68") (name "Net-(S37-Pad1)") (class "Default")
      (node (ref "S37") (pin "1") (pinfunction "1_1") (pintype "passive"))
      (node (ref "S43") (pin "1") (pinfunction "1_1") (pintype "passive"))
      (node (ref "S48") (pin "1") (pinfunction "1_1") (pintype "passive"))
      (node (ref "S53") (pin "1") (pinfunction "1_1") (pintype "passive"))
      (node (ref "S59") (pin "1") (pinfunction "1_1") (pintype "passive"))
      (node (ref "S65") (pin "1") (pinfunction "1_1") (pintype "passive"))
      (node (ref "S71") (pin "1") (pinfunction "1_1") (pintype "passive"))
      (node (ref "f2") (pin "5") (pinfunction "5_5") (pintype "passive"))
    )
    (net (code "69") (name "Net-(S38-Pad1)") (class "Default")
      (node (ref "S38") (pin "1") (pinfunction "1_1") (pintype "passive"))
      (node (ref "S44") (pin "1") (pinfunction "1_1") (pintype "passive"))
      (node (ref "S49") (pin "1") (pinfunction "1_1") (pintype "passive"))
      (node (ref "S54") (pin "1") (pinfunction "1_1") (pintype "passive"))
      (node (ref "S60") (pin "1") (pinfunction "1_1") (pintype "passive"))
      (node (ref "S66") (pin "1") (pinfunction "1_1") (pintype "passive"))
      (node (ref "S83") (pin "1") (pinfunction "1_1") (pintype "passive"))
      (node (ref "f2") (pin "6") (pinfunction "6_6") (pintype "passive"))
    )
    (net (code "70") (name "Net-(S39-Pad1)") (class "Default")
      (node (ref "S39") (pin "1") (pinfunction "1_1") (pintype "passive"))
      (node (ref "S55") (pin "1") (pinfunction "1_1") (pintype "passive"))
      (node (ref "S61") (pin "1") (pinfunction "1_1") (pintype "passive"))
      (node (ref "S67") (pin "1") (pinfunction "1_1") (pintype "passive"))
      (node (ref "S72") (pin "1") (pinfunction "1_1") (pintype "passive"))
      (node (ref "S79") (pin "1") (pinfunction "1_1") (pintype "passive"))
      (node (ref "S84") (pin "1") (pinfunction "1_1") (pintype "passive"))
      (node (ref "S88") (pin "1") (pinfunction "1_1") (pintype "passive"))
      (node (ref "f2") (pin "7") (pinfunction "7_7") (pintype "passive"))
    )
    (net (code "71") (name "Net-(S41-Pad1)") (class "Default")
      (node (ref "S41") (pin "1") (pinfunction "1_1") (pintype "passive"))
      (node (ref "S46") (pin "1") (pinfunction "1_1") (pintype "passive"))
      (node (ref "S51") (pin "1") (pinfunction "1_1") (pintype "passive"))
      (node (ref "S57") (pin "1") (pinfunction "1_1") (pintype "passive"))
      (node (ref "S63") (pin "1") (pinfunction "1_1") (pintype "passive"))
      (node (ref "S69") (pin "1") (pinfunction "1_1") (pintype "passive"))
      (node (ref "S74") (pin "1") (pinfunction "1_1") (pintype "passive"))
      (node (ref "S77") (pin "1") (pinfunction "1_1") (pintype "passive"))
      (node (ref "S81") (pin "1") (pinfunction "1_1") (pintype "passive"))
      (node (ref "S86") (pin "1") (pinfunction "1_1") (pintype "passive"))
      (node (ref "f2") (pin "2") (pinfunction "2_2") (pintype "passive"))
    )
    (net (code "72") (name "unconnected-(f2-Pad8)") (class "Default")
      (node (ref "f2") (pin "8") (pinfunction "8_8") (pintype "passive"))
    )
  )
)
